# motor.net
KiCad netlist of a schematic drawn in EAGLE
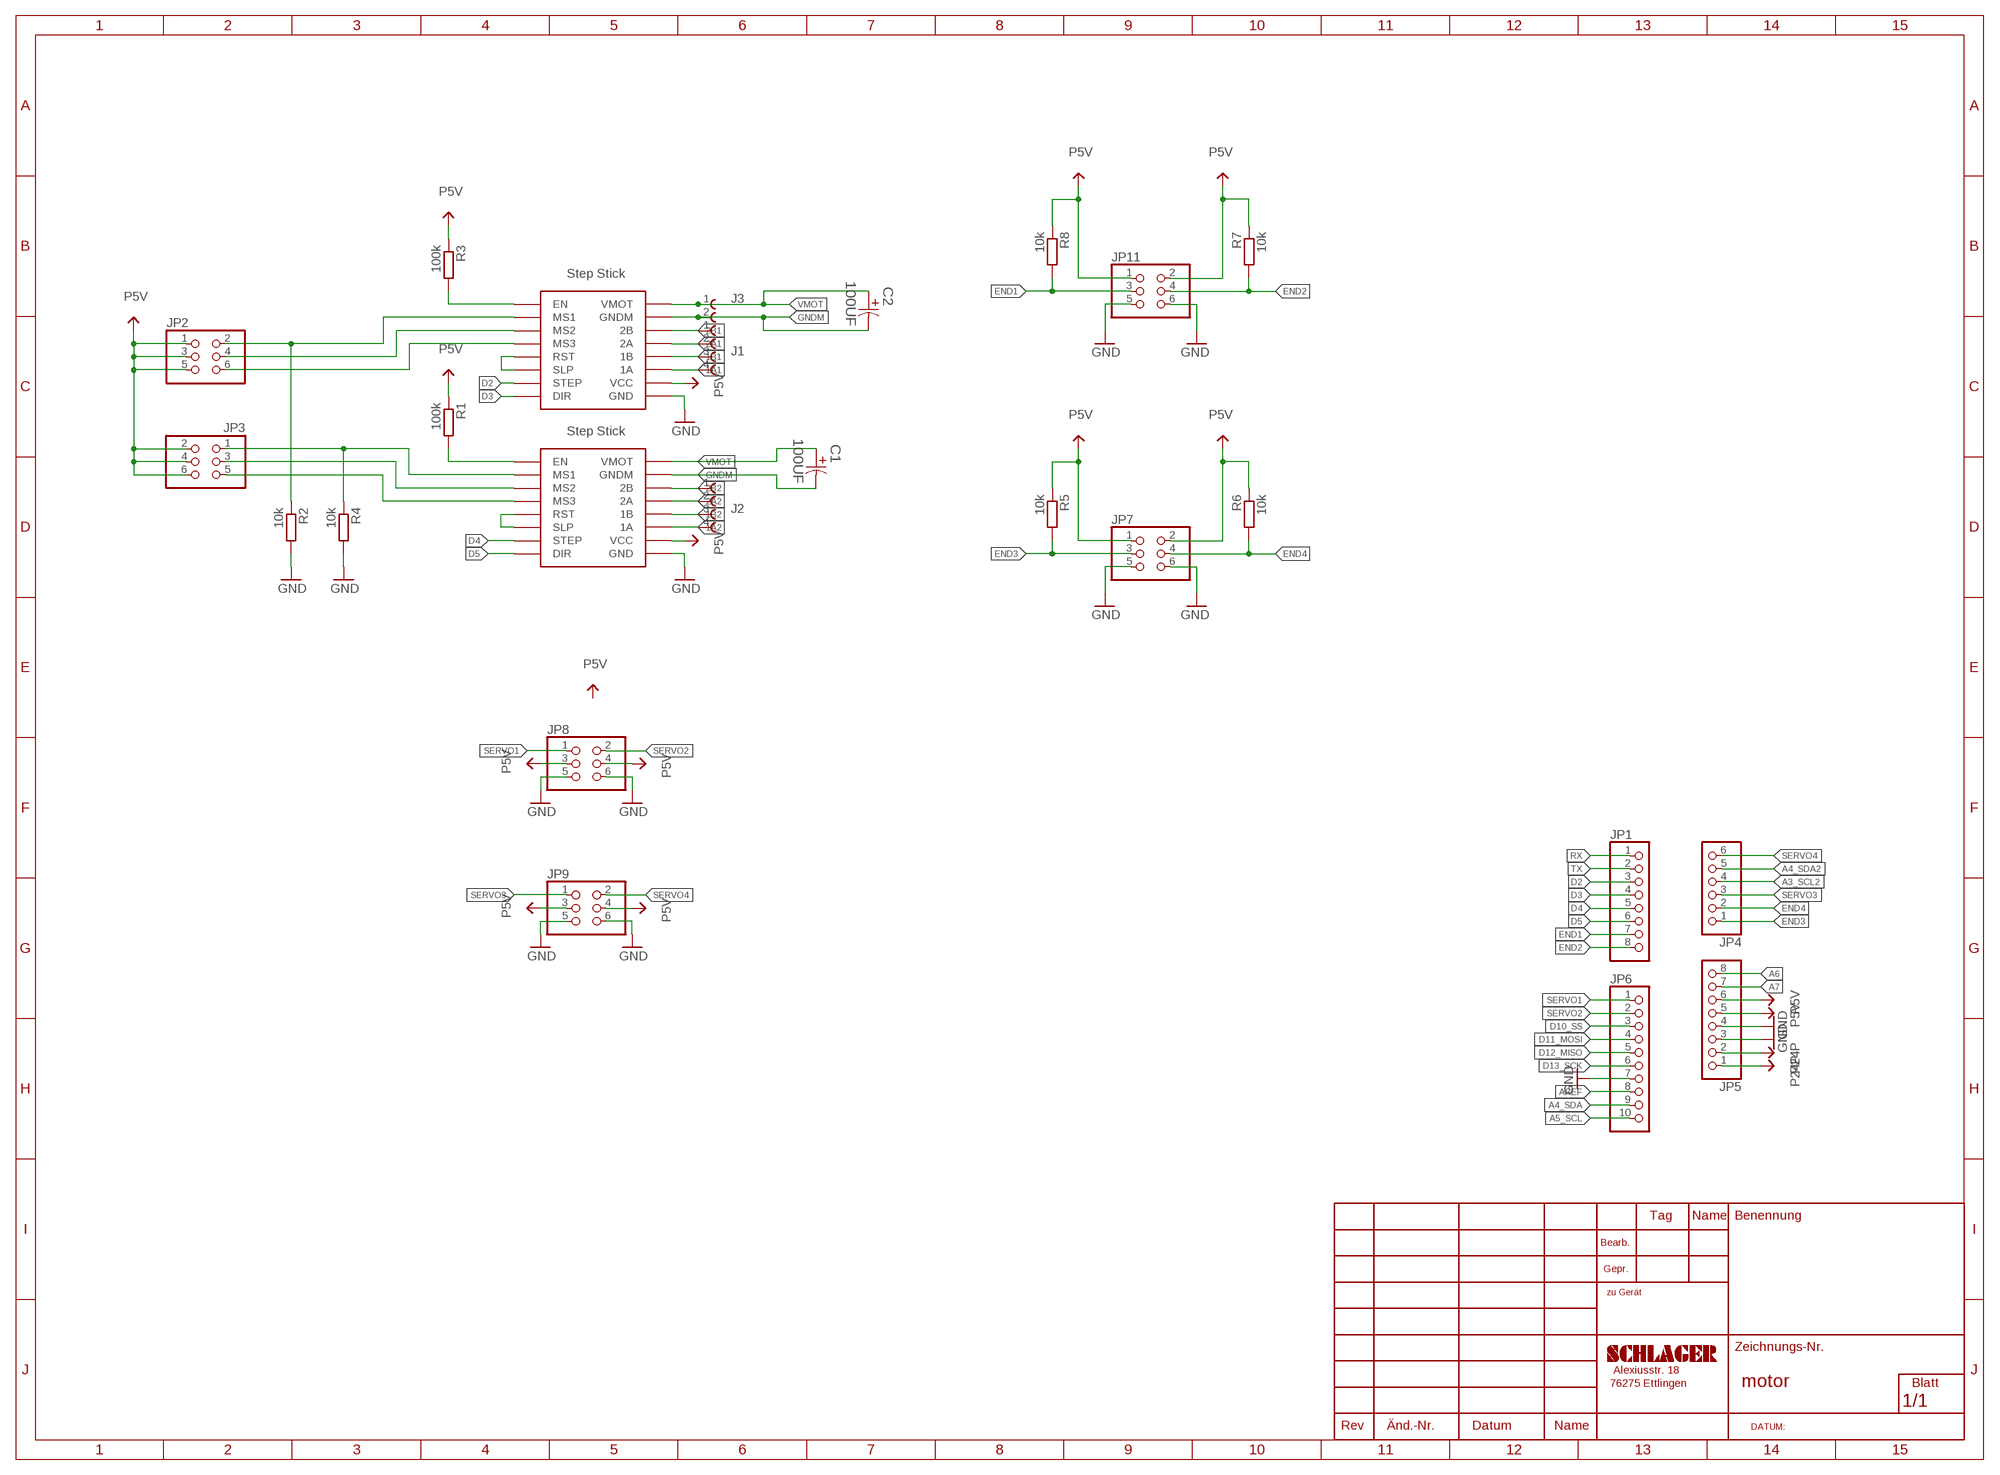
[diagram p0: schematic, sheet 1]

(export (version "E")
  (design (tool "Eeschema 10.0.6"))
  (components
    (comp (ref "C1")
      (value "100UF")
      (footprint "eagle-import:CAPAE830X1050N")
      (fields (field (name "MPN") "EEE-FK1V101P") (field (name "TOLERANCE") "±20 %"))
      (libsource (lib "eagle-import") (part "EEE--CASE-FFK1V101P"))
    )
    (comp (ref "C2")
      (value "100UF")
      (footprint "eagle-import:CAPAE830X1050N")
      (fields (field (name "MPN") "EEE-FK1V101P") (field (name "TOLERANCE") "±20 %"))
      (libsource (lib "eagle-import") (part "EEE--CASE-FFK1V101P"))
    )
    (comp (ref "J1")
      (value "691312510004")
      (footprint "eagle-import:691312510004")
      (libsource (lib "eagle-import") (part "691312510004"))
    )
    (comp (ref "J2")
      (value "691312510004")
      (footprint "eagle-import:691312510004")
      (libsource (lib "eagle-import") (part "691312510004"))
    )
    (comp (ref "J3")
      (value "691312510002")
      (footprint "eagle-import:691312510002")
      (libsource (lib "eagle-import") (part "691312510002"))
    )
    (comp (ref "JP1")
      (value "PINHD-1X8")
      (footprint "eagle-import:1X08")
      (libsource (lib "eagle-import") (part "PINHD-1X8"))
    )
    (comp (ref "JP2")
      (value "PINHD-2X3")
      (footprint "eagle-import:2X03")
      (libsource (lib "eagle-import") (part "PINHD-2X3"))
    )
    (comp (ref "JP3")
      (value "PINHD-2X3")
      (footprint "eagle-import:2X03")
      (libsource (lib "eagle-import") (part "PINHD-2X3"))
    )
    (comp (ref "JP4")
      (value "PINHD-1X6")
      (footprint "eagle-import:1X06")
      (libsource (lib "eagle-import") (part "PINHD-1X6"))
    )
    (comp (ref "JP5")
      (value "PINHD-1X8")
      (footprint "eagle-import:1X08")
      (libsource (lib "eagle-import") (part "PINHD-1X8"))
    )
    (comp (ref "JP6")
      (value "PINHD-1X10")
      (footprint "eagle-import:1X10")
      (libsource (lib "eagle-import") (part "PINHD-1X10"))
    )
    (comp (ref "JP7")
      (value "PINHD-2X3/90")
      (footprint "eagle-import:2X03_90")
      (libsource (lib "eagle-import") (part "PINHD-2X3/90"))
    )
    (comp (ref "JP8")
      (value "PINHD-2X3/90")
      (footprint "eagle-import:2X03_90")
      (libsource (lib "eagle-import") (part "PINHD-2X3/90"))
    )
    (comp (ref "JP9")
      (value "PINHD-2X3/90")
      (footprint "eagle-import:2X03_90")
      (libsource (lib "eagle-import") (part "PINHD-2X3/90"))
    )
    (comp (ref "JP11")
      (value "PINHD-2X3/90")
      (footprint "eagle-import:2X03_90")
      (libsource (lib "eagle-import") (part "PINHD-2X3/90"))
    )
    (comp (ref "R1")
      (value "100k")
      (footprint "eagle-import:R0805")
      (libsource (lib "eagle-import") (part "R-EU_R0805"))
    )
    (comp (ref "R2")
      (value "10k")
      (footprint "eagle-import:R0805")
      (libsource (lib "eagle-import") (part "R-EU_R0805"))
    )
    (comp (ref "R3")
      (value "100k")
      (footprint "eagle-import:R0805")
      (libsource (lib "eagle-import") (part "R-EU_R0805"))
    )
    (comp (ref "R4")
      (value "10k")
      (footprint "eagle-import:R0805")
      (libsource (lib "eagle-import") (part "R-EU_R0805"))
    )
    (comp (ref "R5")
      (value "10k")
      (footprint "eagle-import:R0805")
      (libsource (lib "eagle-import") (part "R-EU_R0805"))
    )
    (comp (ref "R6")
      (value "10k")
      (footprint "eagle-import:R0805")
      (libsource (lib "eagle-import") (part "R-EU_R0805"))
    )
    (comp (ref "R7")
      (value "10k")
      (footprint "eagle-import:R0805")
      (libsource (lib "eagle-import") (part "R-EU_R0805"))
    )
    (comp (ref "R8")
      (value "10k")
      (footprint "eagle-import:R0805")
      (libsource (lib "eagle-import") (part "R-EU_R0805"))
    )
    (comp (ref "U$1")
      (value "STEP-STICK")
      (footprint "eagle-import:STEP-STICK")
      (libsource (lib "eagle-import") (part "STEP-STICK"))
    )
    (comp (ref "U$2")
      (value "STEP-STICK")
      (footprint "eagle-import:STEP-STICK")
      (libsource (lib "eagle-import") (part "STEP-STICK"))
    )
  )
  (nets
    (net (code "1") (name "1A1") (class "Default")
      (node (ref "J1") (pin "4") (pinfunction "4_4") (pintype "passive"))
      (node (ref "U$2") (pin "1A") (pinfunction "1A_1A") (pintype "bidirectional"))
    )
    (net (code "2") (name "1A2") (class "Default")
      (node (ref "J2") (pin "4") (pinfunction "4_4") (pintype "passive"))
      (node (ref "U$1") (pin "1A") (pinfunction "1A_1A") (pintype "bidirectional"))
    )
    (net (code "3") (name "1B1") (class "Default")
      (node (ref "J1") (pin "3") (pinfunction "3_3") (pintype "passive"))
      (node (ref "U$2") (pin "1B") (pinfunction "1B_1B") (pintype "bidirectional"))
    )
    (net (code "4") (name "1B2") (class "Default")
      (node (ref "J2") (pin "3") (pinfunction "3_3") (pintype "passive"))
      (node (ref "U$1") (pin "1B") (pinfunction "1B_1B") (pintype "bidirectional"))
    )
    (net (code "5") (name "2A1") (class "Default")
      (node (ref "J1") (pin "2") (pinfunction "2_2") (pintype "passive"))
      (node (ref "U$2") (pin "2A") (pinfunction "2A_2A") (pintype "bidirectional"))
    )
    (net (code "6") (name "2A2") (class "Default")
      (node (ref "J2") (pin "2") (pinfunction "2_2") (pintype "passive"))
      (node (ref "U$1") (pin "2A") (pinfunction "2A_2A") (pintype "bidirectional"))
    )
    (net (code "7") (name "2B1") (class "Default")
      (node (ref "J1") (pin "1") (pinfunction "1_1") (pintype "passive"))
      (node (ref "U$2") (pin "2B") (pinfunction "2B_2B") (pintype "bidirectional"))
    )
    (net (code "8") (name "2B2") (class "Default")
      (node (ref "J2") (pin "1") (pinfunction "1_1") (pintype "passive"))
      (node (ref "U$1") (pin "2B") (pinfunction "2B_2B") (pintype "bidirectional"))
    )
    (net (code "9") (name "A3_SCL2") (class "Default")
      (node (ref "JP4") (pin "4") (pinfunction "4_4") (pintype "passive"))
    )
    (net (code "10") (name "A4_SDA") (class "Default")
      (node (ref "JP6") (pin "9") (pinfunction "9_9") (pintype "passive"))
    )
    (net (code "11") (name "A4_SDA2") (class "Default")
      (node (ref "JP4") (pin "5") (pinfunction "5_5") (pintype "passive"))
    )
    (net (code "12") (name "A5_SCL") (class "Default")
      (node (ref "JP6") (pin "10") (pinfunction "10_10") (pintype "passive"))
    )
    (net (code "13") (name "A6") (class "Default")
      (node (ref "JP5") (pin "8") (pinfunction "8_8") (pintype "passive"))
    )
    (net (code "14") (name "A7") (class "Default")
      (node (ref "JP5") (pin "7") (pinfunction "7_7") (pintype "passive"))
    )
    (net (code "15") (name "AREF") (class "Default")
      (node (ref "JP6") (pin "8") (pinfunction "8_8") (pintype "passive"))
    )
    (net (code "16") (name "D2") (class "Default")
      (node (ref "JP1") (pin "3") (pinfunction "3_3") (pintype "passive"))
      (node (ref "U$2") (pin "SPT") (pinfunction "STEP_SPT") (pintype "bidirectional"))
    )
    (net (code "17") (name "D3") (class "Default")
      (node (ref "JP1") (pin "4") (pinfunction "4_4") (pintype "passive"))
      (node (ref "U$2") (pin "DIR") (pinfunction "DIR_DIR") (pintype "bidirectional"))
    )
    (net (code "18") (name "D4") (class "Default")
      (node (ref "JP1") (pin "5") (pinfunction "5_5") (pintype "passive"))
      (node (ref "U$1") (pin "SPT") (pinfunction "STEP_SPT") (pintype "bidirectional"))
    )
    (net (code "19") (name "D5") (class "Default")
      (node (ref "JP1") (pin "6") (pinfunction "6_6") (pintype "passive"))
      (node (ref "U$1") (pin "DIR") (pinfunction "DIR_DIR") (pintype "bidirectional"))
    )
    (net (code "20") (name "D10_SS") (class "Default")
      (node (ref "JP6") (pin "3") (pinfunction "3_3") (pintype "passive"))
    )
    (net (code "21") (name "D11_MOSI") (class "Default")
      (node (ref "JP6") (pin "4") (pinfunction "4_4") (pintype "passive"))
    )
    (net (code "22") (name "D12_MISO") (class "Default")
      (node (ref "JP6") (pin "5") (pinfunction "5_5") (pintype "passive"))
    )
    (net (code "23") (name "D13_SCK") (class "Default")
      (node (ref "JP6") (pin "6") (pinfunction "6_6") (pintype "passive"))
    )
    (net (code "24") (name "END1") (class "Default")
      (node (ref "JP1") (pin "7") (pinfunction "7_7") (pintype "passive"))
      (node (ref "JP11") (pin "3") (pinfunction "3_3") (pintype "passive"))
      (node (ref "R8") (pin "2") (pinfunction "2_2") (pintype "passive"))
    )
    (net (code "25") (name "END2") (class "Default")
      (node (ref "JP1") (pin "8") (pinfunction "8_8") (pintype "passive"))
      (node (ref "JP11") (pin "4") (pinfunction "4_4") (pintype "passive"))
      (node (ref "R7") (pin "2") (pinfunction "2_2") (pintype "passive"))
    )
    (net (code "26") (name "END3") (class "Default")
      (node (ref "JP4") (pin "1") (pinfunction "1_1") (pintype "passive"))
      (node (ref "JP7") (pin "3") (pinfunction "3_3") (pintype "passive"))
      (node (ref "R5") (pin "2") (pinfunction "2_2") (pintype "passive"))
    )
    (net (code "27") (name "END4") (class "Default")
      (node (ref "JP4") (pin "2") (pinfunction "2_2") (pintype "passive"))
      (node (ref "JP7") (pin "4") (pinfunction "4_4") (pintype "passive"))
      (node (ref "R6") (pin "2") (pinfunction "2_2") (pintype "passive"))
    )
    (net (code "28") (name "GND") (class "Default")
      (node (ref "JP11") (pin "5") (pinfunction "5_5") (pintype "passive"))
      (node (ref "JP11") (pin "6") (pinfunction "6_6") (pintype "passive"))
      (node (ref "JP5") (pin "3") (pinfunction "3_3") (pintype "passive"))
      (node (ref "JP5") (pin "4") (pinfunction "4_4") (pintype "passive"))
      (node (ref "JP6") (pin "7") (pinfunction "7_7") (pintype "passive"))
      (node (ref "JP7") (pin "5") (pinfunction "5_5") (pintype "passive"))
      (node (ref "JP7") (pin "6") (pinfunction "6_6") (pintype "passive"))
      (node (ref "JP8") (pin "5") (pinfunction "5_5") (pintype "passive"))
      (node (ref "JP8") (pin "6") (pinfunction "6_6") (pintype "passive"))
      (node (ref "JP9") (pin "5") (pinfunction "5_5") (pintype "passive"))
      (node (ref "JP9") (pin "6") (pinfunction "6_6") (pintype "passive"))
      (node (ref "R2") (pin "2") (pinfunction "2_2") (pintype "passive"))
      (node (ref "R4") (pin "2") (pinfunction "2_2") (pintype "passive"))
      (node (ref "U$1") (pin "GND") (pinfunction "GND_GND") (pintype "bidirectional"))
      (node (ref "U$2") (pin "GND") (pinfunction "GND_GND") (pintype "bidirectional"))
    )
    (net (code "29") (name "GNDM") (class "Default")
      (node (ref "C1") (pin "2") (pinfunction "2_2") (pintype "passive"))
      (node (ref "C2") (pin "2") (pinfunction "2_2") (pintype "passive"))
      (node (ref "J3") (pin "2") (pinfunction "2_2") (pintype "passive"))
      (node (ref "U$1") (pin "GNDM") (pinfunction "GNDM_GNDM") (pintype "bidirectional"))
      (node (ref "U$2") (pin "GNDM") (pinfunction "GNDM_GNDM") (pintype "bidirectional"))
    )
    (net (code "30") (name "Net-(JP2-Pad2)") (class "Default")
      (node (ref "JP2") (pin "2") (pinfunction "2_2") (pintype "passive"))
      (node (ref "R2") (pin "1") (pinfunction "1_1") (pintype "passive"))
      (node (ref "U$2") (pin "MS1") (pinfunction "MS1_MS1") (pintype "bidirectional"))
    )
    (net (code "31") (name "Net-(JP2-Pad4)") (class "Default")
      (node (ref "JP2") (pin "4") (pinfunction "4_4") (pintype "passive"))
      (node (ref "U$2") (pin "MS2") (pinfunction "MS2_MS2") (pintype "bidirectional"))
    )
    (net (code "32") (name "Net-(JP2-Pad6)") (class "Default")
      (node (ref "JP2") (pin "6") (pinfunction "6_6") (pintype "passive"))
      (node (ref "U$2") (pin "MS3") (pinfunction "MS3_MS3") (pintype "bidirectional"))
    )
    (net (code "33") (name "Net-(JP3-Pad1)") (class "Default")
      (node (ref "JP3") (pin "1") (pinfunction "1_1") (pintype "passive"))
      (node (ref "R4") (pin "1") (pinfunction "1_1") (pintype "passive"))
      (node (ref "U$1") (pin "MS1") (pinfunction "MS1_MS1") (pintype "bidirectional"))
    )
    (net (code "34") (name "Net-(JP3-Pad3)") (class "Default")
      (node (ref "JP3") (pin "3") (pinfunction "3_3") (pintype "passive"))
      (node (ref "U$1") (pin "MS2") (pinfunction "MS2_MS2") (pintype "bidirectional"))
    )
    (net (code "35") (name "Net-(JP3-Pad5)") (class "Default")
      (node (ref "JP3") (pin "5") (pinfunction "5_5") (pintype "passive"))
      (node (ref "U$1") (pin "MS3") (pinfunction "MS3_MS3") (pintype "bidirectional"))
    )
    (net (code "36") (name "Net-(R1-Pad2)") (class "Default")
      (node (ref "R1") (pin "2") (pinfunction "2_2") (pintype "passive"))
      (node (ref "U$1") (pin "EN") (pinfunction "EN_EN") (pintype "bidirectional"))
    )
    (net (code "37") (name "Net-(R3-Pad2)") (class "Default")
      (node (ref "R3") (pin "2") (pinfunction "2_2") (pintype "passive"))
      (node (ref "U$2") (pin "EN") (pinfunction "EN_EN") (pintype "bidirectional"))
    )
    (net (code "38") (name "Net-(U$1-PadRST)") (class "Default")
      (node (ref "U$1") (pin "RST") (pinfunction "RST_RST") (pintype "bidirectional"))
      (node (ref "U$1") (pin "SLP") (pinfunction "SLP_SLP") (pintype "bidirectional"))
    )
    (net (code "39") (name "Net-(U$2-PadRST)") (class "Default")
      (node (ref "U$2") (pin "RST") (pinfunction "RST_RST") (pintype "bidirectional"))
      (node (ref "U$2") (pin "SLP") (pinfunction "SLP_SLP") (pintype "bidirectional"))
    )
    (net (code "40") (name "P5V") (class "Default")
      (node (ref "JP11") (pin "1") (pinfunction "1_1") (pintype "passive"))
      (node (ref "JP11") (pin "2") (pinfunction "2_2") (pintype "passive"))
      (node (ref "JP2") (pin "1") (pinfunction "1_1") (pintype "passive"))
      (node (ref "JP2") (pin "3") (pinfunction "3_3") (pintype "passive"))
      (node (ref "JP2") (pin "5") (pinfunction "5_5") (pintype "passive"))
      (node (ref "JP3") (pin "2") (pinfunction "2_2") (pintype "passive"))
      (node (ref "JP3") (pin "4") (pinfunction "4_4") (pintype "passive"))
      (node (ref "JP3") (pin "6") (pinfunction "6_6") (pintype "passive"))
      (node (ref "JP5") (pin "5") (pinfunction "5_5") (pintype "passive"))
      (node (ref "JP5") (pin "6") (pinfunction "6_6") (pintype "passive"))
      (node (ref "JP7") (pin "1") (pinfunction "1_1") (pintype "passive"))
      (node (ref "JP7") (pin "2") (pinfunction "2_2") (pintype "passive"))
      (node (ref "JP8") (pin "3") (pinfunction "3_3") (pintype "passive"))
      (node (ref "JP8") (pin "4") (pinfunction "4_4") (pintype "passive"))
      (node (ref "JP9") (pin "3") (pinfunction "3_3") (pintype "passive"))
      (node (ref "JP9") (pin "4") (pinfunction "4_4") (pintype "passive"))
      (node (ref "R1") (pin "1") (pinfunction "1_1") (pintype "passive"))
      (node (ref "R3") (pin "1") (pinfunction "1_1") (pintype "passive"))
      (node (ref "R5") (pin "1") (pinfunction "1_1") (pintype "passive"))
      (node (ref "R6") (pin "1") (pinfunction "1_1") (pintype "passive"))
      (node (ref "R7") (pin "1") (pinfunction "1_1") (pintype "passive"))
      (node (ref "R8") (pin "1") (pinfunction "1_1") (pintype "passive"))
      (node (ref "U$1") (pin "VCC") (pinfunction "VCC_VCC") (pintype "bidirectional"))
      (node (ref "U$2") (pin "VCC") (pinfunction "VCC_VCC") (pintype "bidirectional"))
    )
    (net (code "41") (name "P24P") (class "Default")
      (node (ref "JP5") (pin "1") (pinfunction "1_1") (pintype "passive"))
      (node (ref "JP5") (pin "2") (pinfunction "2_2") (pintype "passive"))
    )
    (net (code "42") (name "RX") (class "Default")
      (node (ref "JP1") (pin "1") (pinfunction "1_1") (pintype "passive"))
    )
    (net (code "43") (name "SERVO1") (class "Default")
      (node (ref "JP6") (pin "1") (pinfunction "1_1") (pintype "passive"))
      (node (ref "JP8") (pin "1") (pinfunction "1_1") (pintype "passive"))
    )
    (net (code "44") (name "SERVO2") (class "Default")
      (node (ref "JP6") (pin "2") (pinfunction "2_2") (pintype "passive"))
      (node (ref "JP8") (pin "2") (pinfunction "2_2") (pintype "passive"))
    )
    (net (code "45") (name "SERVO3") (class "Default")
      (node (ref "JP4") (pin "3") (pinfunction "3_3") (pintype "passive"))
      (node (ref "JP9") (pin "1") (pinfunction "1_1") (pintype "passive"))
    )
    (net (code "46") (name "SERVO4") (class "Default")
      (node (ref "JP4") (pin "6") (pinfunction "6_6") (pintype "passive"))
      (node (ref "JP9") (pin "2") (pinfunction "2_2") (pintype "passive"))
    )
    (net (code "47") (name "TX") (class "Default")
      (node (ref "JP1") (pin "2") (pinfunction "2_2") (pintype "passive"))
    )
    (net (code "48") (name "VMOT") (class "Default")
      (node (ref "C1") (pin "1") (pinfunction "1_1") (pintype "passive"))
      (node (ref "C2") (pin "1") (pinfunction "1_1") (pintype "passive"))
      (node (ref "J3") (pin "1") (pinfunction "1_1") (pintype "passive"))
      (node (ref "U$1") (pin "VMOT") (pinfunction "VMOT_VMOT") (pintype "bidirectional"))
      (node (ref "U$2") (pin "VMOT") (pinfunction "VMOT_VMOT") (pintype "bidirectional"))
    )
  )
)
